# RF_SHIELD.net
KiCad netlist of a schematic drawn in Altium Designer
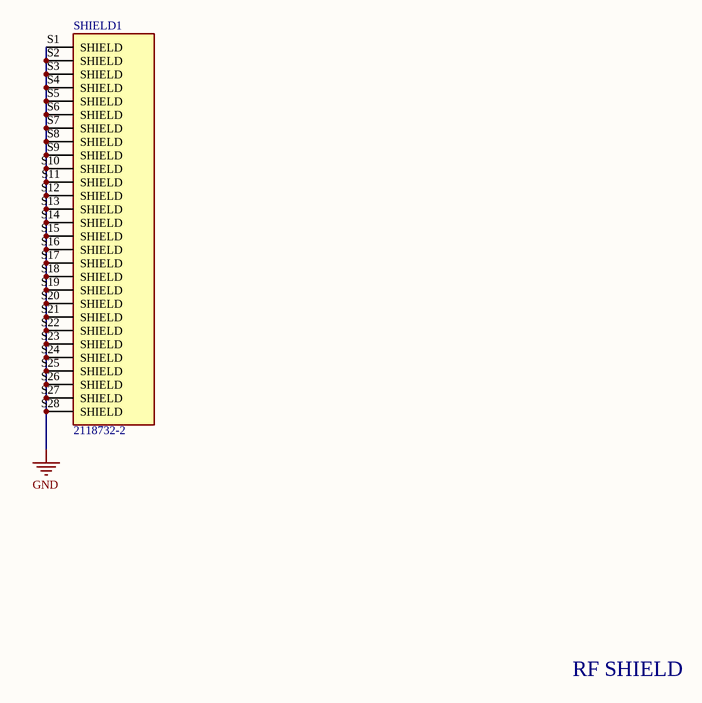
[diagram p0: RF SHIELD.SchDoc]

(export (version "E")
  (design (tool "Eeschema 10.0.6"))
  (components
    (comp (ref "SHIELD1")
      (value "2118732-2")
      (footprint "TE_2118732-2")
      (description "EMI Filters; Board Level Shielding (BLS); STD SHIELD FRAME; CRS-50.80X38.10X5.08MM")
      (fields (field (name "MF") "TE Connectivity"))
      (libsource (lib "2118732-2") (part "2118732-2"))
    )
  )
  (nets
    (net (code "1") (name "GND") (class "Default")
      (node (ref "SHIELD1") (pin "S1") (pinfunction "SHIELD_S1") (pintype "passive"))
      (node (ref "SHIELD1") (pin "S10") (pinfunction "SHIELD_S10") (pintype "passive"))
      (node (ref "SHIELD1") (pin "S11") (pinfunction "SHIELD_S11") (pintype "passive"))
      (node (ref "SHIELD1") (pin "S12") (pinfunction "SHIELD_S12") (pintype "passive"))
      (node (ref "SHIELD1") (pin "S13") (pinfunction "SHIELD_S13") (pintype "passive"))
      (node (ref "SHIELD1") (pin "S14") (pinfunction "SHIELD_S14") (pintype "passive"))
      (node (ref "SHIELD1") (pin "S15") (pinfunction "SHIELD_S15") (pintype "passive"))
      (node (ref "SHIELD1") (pin "S16") (pinfunction "SHIELD_S16") (pintype "passive"))
      (node (ref "SHIELD1") (pin "S17") (pinfunction "SHIELD_S17") (pintype "passive"))
      (node (ref "SHIELD1") (pin "S18") (pinfunction "SHIELD_S18") (pintype "passive"))
      (node (ref "SHIELD1") (pin "S19") (pinfunction "SHIELD_S19") (pintype "passive"))
      (node (ref "SHIELD1") (pin "S2") (pinfunction "SHIELD_S2") (pintype "passive"))
      (node (ref "SHIELD1") (pin "S20") (pinfunction "SHIELD_S20") (pintype "passive"))
      (node (ref "SHIELD1") (pin "S21") (pinfunction "SHIELD_S21") (pintype "passive"))
      (node (ref "SHIELD1") (pin "S22") (pinfunction "SHIELD_S22") (pintype "passive"))
      (node (ref "SHIELD1") (pin "S23") (pinfunction "SHIELD_S23") (pintype "passive"))
      (node (ref "SHIELD1") (pin "S24") (pinfunction "SHIELD_S24") (pintype "passive"))
      (node (ref "SHIELD1") (pin "S25") (pinfunction "SHIELD_S25") (pintype "passive"))
      (node (ref "SHIELD1") (pin "S26") (pinfunction "SHIELD_S26") (pintype "passive"))
      (node (ref "SHIELD1") (pin "S27") (pinfunction "SHIELD_S27") (pintype "passive"))
      (node (ref "SHIELD1") (pin "S28") (pinfunction "SHIELD_S28") (pintype "passive"))
      (node (ref "SHIELD1") (pin "S3") (pinfunction "SHIELD_S3") (pintype "passive"))
      (node (ref "SHIELD1") (pin "S4") (pinfunction "SHIELD_S4") (pintype "passive"))
      (node (ref "SHIELD1") (pin "S5") (pinfunction "SHIELD_S5") (pintype "passive"))
      (node (ref "SHIELD1") (pin "S6") (pinfunction "SHIELD_S6") (pintype "passive"))
      (node (ref "SHIELD1") (pin "S7") (pinfunction "SHIELD_S7") (pintype "passive"))
      (node (ref "SHIELD1") (pin "S8") (pinfunction "SHIELD_S8") (pintype "passive"))
      (node (ref "SHIELD1") (pin "S9") (pinfunction "SHIELD_S9") (pintype "passive"))
    )
  )
)
